# SpannungssensorTP.net
KiCad netlist of a schematic drawn in Altium Designer
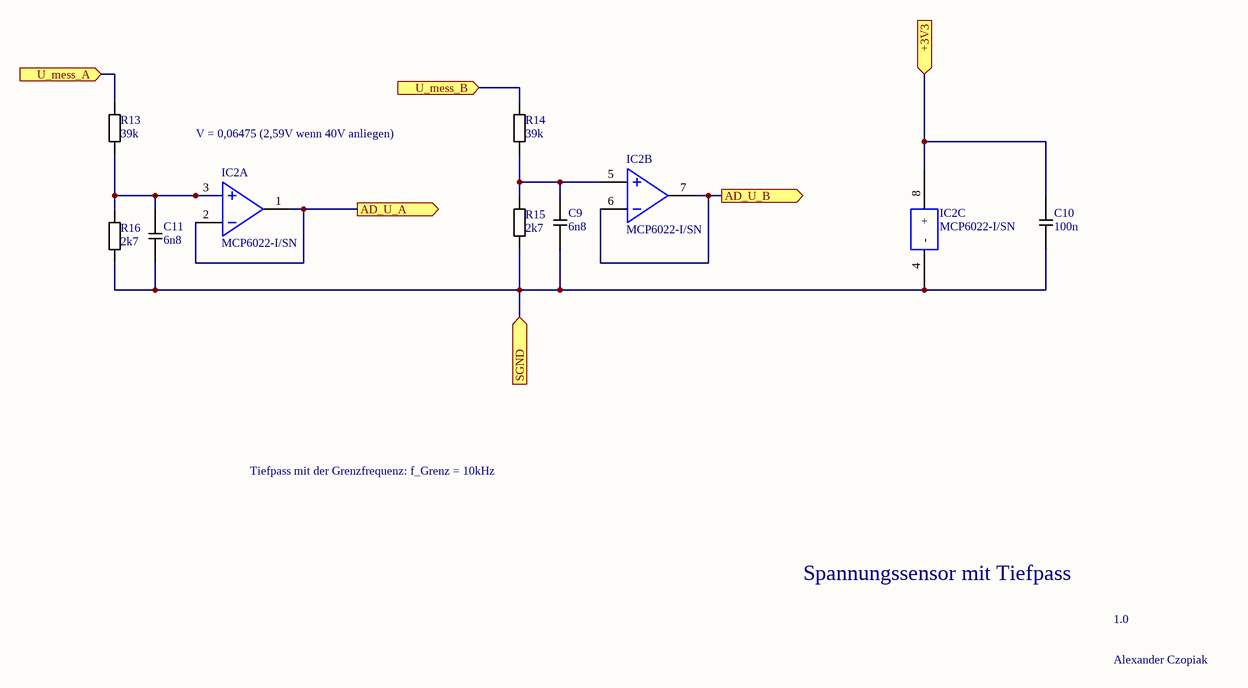
[diagram p0: SpannungssensorTP.SchDoc]

(export (version "E")
  (design (tool "Eeschema 10.0.6"))
  (components
    (comp (ref "C9")
      (value "6n8")
      (footprint "1206_C")
      (description "Kondensator (ohne Polarität)")
      (libsource (lib "HSLS_Parts") (part "CAP"))
    )
    (comp (ref "C10")
      (value "100n")
      (footprint "1206_C")
      (description "Kondensator (ohne Polarität)")
      (libsource (lib "HSLS_Parts") (part "CAP"))
    )
    (comp (ref "C11")
      (value "6n8")
      (footprint "1206_C")
      (description "Kondensator (ohne Polarität)")
      (libsource (lib "HSLS_Parts") (part "CAP"))
    )
    (comp (ref "IC2")
      (value "MCP6022-I/SN")
      (footprint "SO08_N")
      (libsource (lib "HSLS_Parts") (part "MCP6022-I/SN"))
    )
    (comp (ref "R13")
      (value "39k")
      (footprint "1206_R")
      (description "Widerstand")
      (libsource (lib "HSLS_Parts") (part "WIDERSTAND"))
    )
    (comp (ref "R14")
      (value "39k")
      (footprint "1206_R")
      (description "Widerstand")
      (libsource (lib "HSLS_Parts") (part "WIDERSTAND"))
    )
    (comp (ref "R15")
      (value "2k7")
      (footprint "1206_R")
      (description "Widerstand")
      (libsource (lib "HSLS_Parts") (part "WIDERSTAND"))
    )
    (comp (ref "R16")
      (value "2k7")
      (footprint "1206_R")
      (description "Widerstand")
      (libsource (lib "HSLS_Parts") (part "WIDERSTAND"))
    )
  )
  (nets
    (net (code "1") (name "/+3V3") (class "Default")
      (node (ref "C10") (pin "2") (pinfunction "2_2") (pintype "passive"))
      (node (ref "IC2") (pin "8") (pinfunction "+_8") (pintype "passive"))
    )
    (net (code "2") (name "/AD_U_A") (class "Default")
      (node (ref "IC2") (pin "1") (pintype "passive"))
      (node (ref "IC2") (pin "2") (pintype "passive"))
    )
    (net (code "3") (name "/AD_U_B") (class "Default")
      (node (ref "IC2") (pin "6") (pintype "passive"))
      (node (ref "IC2") (pin "7") (pintype "passive"))
    )
    (net (code "4") (name "/SGND") (class "Default")
      (node (ref "C10") (pin "1") (pinfunction "1_1") (pintype "passive"))
      (node (ref "C11") (pin "1") (pinfunction "1_1") (pintype "passive"))
      (node (ref "C9") (pin "1") (pinfunction "1_1") (pintype "passive"))
      (node (ref "IC2") (pin "4") (pinfunction "-_4") (pintype "passive"))
      (node (ref "R15") (pin "1") (pinfunction "1_1") (pintype "passive"))
      (node (ref "R16") (pin "1") (pinfunction "1_1") (pintype "passive"))
    )
    (net (code "5") (name "/U_mess_A") (class "Default")
      (node (ref "R13") (pin "2") (pinfunction "2_2") (pintype "passive"))
    )
    (net (code "6") (name "/U_mess_B") (class "Default")
      (node (ref "R14") (pin "2") (pinfunction "2_2") (pintype "passive"))
    )
    (net (code "7") (name "Net-(C9-Pad2)") (class "Default")
      (node (ref "C9") (pin "2") (pinfunction "2_2") (pintype "passive"))
      (node (ref "IC2") (pin "5") (pintype "passive"))
      (node (ref "R14") (pin "1") (pinfunction "1_1") (pintype "passive"))
      (node (ref "R15") (pin "2") (pinfunction "2_2") (pintype "passive"))
    )
    (net (code "8") (name "Net-(C11-Pad2)") (class "Default")
      (node (ref "C11") (pin "2") (pinfunction "2_2") (pintype "passive"))
      (node (ref "IC2") (pin "3") (pintype "passive"))
      (node (ref "R13") (pin "1") (pinfunction "1_1") (pintype "passive"))
      (node (ref "R16") (pin "2") (pinfunction "2_2") (pintype "passive"))
    )
  )
)
